# TRV_ANAREN_V0_2.net
KiCad netlist of a schematic drawn in EAGLE
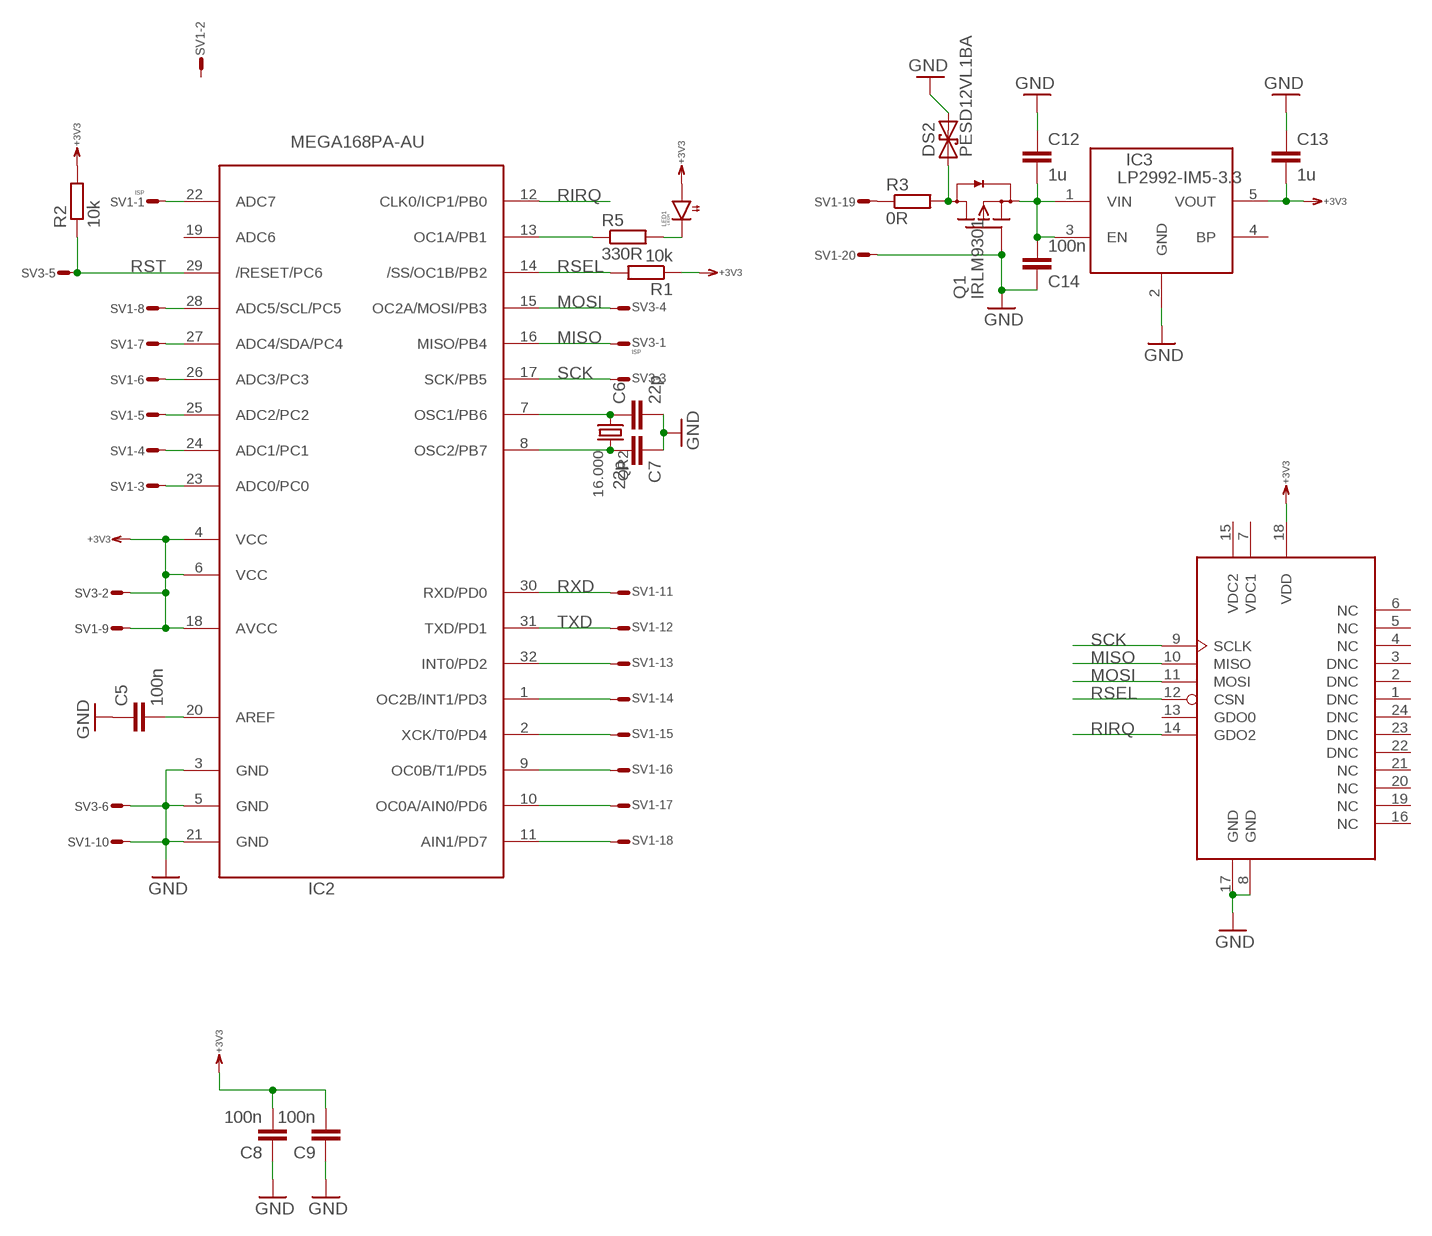
[diagram p0: schematic, sheet 1]

(export (version "E")
  (design (tool "Eeschema 10.0.6"))
  (components
    (comp (ref "C5")
      (value "100n")
      (footprint "eagle-import:0603")
      (libsource (lib "eagle-import") (part "C0603"))
    )
    (comp (ref "C6")
      (value "22p")
      (footprint "eagle-import:0603")
      (libsource (lib "eagle-import") (part "C0603"))
    )
    (comp (ref "C7")
      (value "22p")
      (footprint "eagle-import:0603")
      (libsource (lib "eagle-import") (part "C0603"))
    )
    (comp (ref "C8")
      (value "100n")
      (footprint "eagle-import:0603")
      (libsource (lib "eagle-import") (part "C0603"))
    )
    (comp (ref "C9")
      (value "100n")
      (footprint "eagle-import:0603")
      (libsource (lib "eagle-import") (part "C0603"))
    )
    (comp (ref "C12")
      (value "1u")
      (footprint "eagle-import:0603")
      (libsource (lib "eagle-import") (part "C0603"))
    )
    (comp (ref "C13")
      (value "1u")
      (footprint "eagle-import:0603")
      (libsource (lib "eagle-import") (part "C0603"))
    )
    (comp (ref "C14")
      (value "100n")
      (footprint "eagle-import:0603")
      (libsource (lib "eagle-import") (part "C0603"))
    )
    (comp (ref "DS2")
      (value "PESD12VL1BA")
      (footprint "eagle-import:SOD323")
      (libsource (lib "eagle-import") (part "TVS-U323"))
    )
    (comp (ref "IC2")
      (value "MEGA168PA-AU")
      (footprint "eagle-import:TQFP32-08")
      (libsource (lib "eagle-import") (part "MEGA168PA"))
    )
    (comp (ref "IC3")
      (value "LP2992-IM5-3.3")
      (footprint "eagle-import:SOT23-5")
      (libsource (lib "eagle-import") (part "LDO"))
    )
    (comp (ref "LED1")
      (value "LEDR")
      (footprint "eagle-import:0603")
      (libsource (lib "eagle-import") (part "LED0603"))
    )
    (comp (ref "Q1")
      (value "IRLM9301")
      (footprint "eagle-import:SOT23")
      (libsource (lib "eagle-import") (part "FET-PDSOT23"))
    )
    (comp (ref "QR2")
      (value "16.000")
      (footprint "eagle-import:HC49U-V")
      (libsource (lib "eagle-import") (part "Q49UV"))
    )
    (comp (ref "R1")
      (value "10k")
      (footprint "eagle-import:0603")
      (libsource (lib "eagle-import") (part "R0603"))
    )
    (comp (ref "R2")
      (value "10k")
      (footprint "eagle-import:0603")
      (libsource (lib "eagle-import") (part "R0603"))
    )
    (comp (ref "R3")
      (value "0R")
      (footprint "eagle-import:0603")
      (libsource (lib "eagle-import") (part "R0603"))
    )
    (comp (ref "R5")
      (value "330R")
      (footprint "eagle-import:0603")
      (libsource (lib "eagle-import") (part "R0603"))
    )
    (comp (ref "RF1")
      (value "ANAREN")
      (footprint "eagle-import:ANAREN")
      (libsource (lib "eagle-import") (part "ANAREN"))
    )
    (comp (ref "SV1")
      (value "ISP")
      (footprint "eagle-import:ML20")
      (libsource (lib "eagle-import") (part "ML20?E"))
    )
    (comp (ref "SV3")
      (value "ISP")
      (footprint "eagle-import:ML6")
      (libsource (lib "eagle-import") (part "ML6E"))
    )
  )
  (nets
    (net (code "1") (name "+3V3") (class "Default")
      (node (ref "C13") (pin "2") (pinfunction "2_2") (pintype "passive"))
      (node (ref "C8") (pin "2") (pinfunction "2_2") (pintype "passive"))
      (node (ref "C9") (pin "2") (pinfunction "2_2") (pintype "passive"))
      (node (ref "IC2") (pin "18") (pinfunction "AVCC_18") (pintype "bidirectional"))
      (node (ref "IC2") (pin "4") (pinfunction "VCC_4") (pintype "bidirectional"))
      (node (ref "IC2") (pin "6") (pinfunction "VCC_6") (pintype "bidirectional"))
      (node (ref "IC3") (pin "5") (pinfunction "VOUT_5") (pintype "bidirectional"))
      (node (ref "LED1") (pin "1") (pinfunction "A_1") (pintype "bidirectional"))
      (node (ref "R1") (pin "1") (pinfunction "1_1") (pintype "passive"))
      (node (ref "R2") (pin "2") (pinfunction "2_2") (pintype "passive"))
      (node (ref "RF1") (pin "18") (pinfunction "VDD_18") (pintype "bidirectional"))
      (node (ref "SV1") (pin "9") (pinfunction "S_9") (pintype "passive"))
      (node (ref "SV3") (pin "2") (pinfunction "S_2") (pintype "passive"))
    )
    (net (code "2") (name "/MISO") (class "Default")
      (node (ref "IC2") (pin "16") (pinfunction "MISO/PB4_16") (pintype "bidirectional"))
      (node (ref "RF1") (pin "10") (pinfunction "MISO_10") (pintype "output"))
      (node (ref "SV3") (pin "1") (pinfunction "S_1") (pintype "passive"))
    )
    (net (code "3") (name "/MOSI") (class "Default")
      (node (ref "IC2") (pin "15") (pinfunction "OC2A/MOSI/PB3_15") (pintype "bidirectional"))
      (node (ref "RF1") (pin "11") (pinfunction "MOSI_11") (pintype "input"))
      (node (ref "SV3") (pin "4") (pinfunction "S_4") (pintype "passive"))
    )
    (net (code "4") (name "/RIRQ") (class "Default")
      (node (ref "IC2") (pin "12") (pinfunction "CLK0/ICP1/PB0_12") (pintype "bidirectional"))
      (node (ref "RF1") (pin "14") (pinfunction "GDO2_14") (pintype "bidirectional"))
    )
    (net (code "5") (name "/RSEL") (class "Default")
      (node (ref "IC2") (pin "14") (pinfunction "/SS/OC1B/PB2_14") (pintype "bidirectional"))
      (node (ref "R1") (pin "2") (pinfunction "2_2") (pintype "passive"))
      (node (ref "RF1") (pin "12") (pinfunction "CSN_12") (pintype "input"))
    )
    (net (code "6") (name "/RST") (class "Default")
      (node (ref "IC2") (pin "29") (pinfunction "/RESET/PC6_29") (pintype "bidirectional"))
      (node (ref "R2") (pin "1") (pinfunction "1_1") (pintype "passive"))
      (node (ref "SV3") (pin "5") (pinfunction "S_5") (pintype "passive"))
    )
    (net (code "7") (name "/RXD") (class "Default")
      (node (ref "IC2") (pin "30") (pinfunction "RXD/PD0_30") (pintype "bidirectional"))
      (node (ref "SV1") (pin "11") (pinfunction "S_11") (pintype "passive"))
    )
    (net (code "8") (name "/SCK") (class "Default")
      (node (ref "IC2") (pin "17") (pinfunction "SCK/PB5_17") (pintype "bidirectional"))
      (node (ref "RF1") (pin "9") (pinfunction "SCLK_9") (pintype "input"))
      (node (ref "SV3") (pin "3") (pinfunction "S_3") (pintype "passive"))
    )
    (net (code "9") (name "/TXD") (class "Default")
      (node (ref "IC2") (pin "31") (pinfunction "TXD/PD1_31") (pintype "bidirectional"))
      (node (ref "SV1") (pin "12") (pinfunction "S_12") (pintype "passive"))
    )
    (net (code "10") (name "GND") (class "Default")
      (node (ref "C12") (pin "1") (pinfunction "1_1") (pintype "passive"))
      (node (ref "C13") (pin "1") (pinfunction "1_1") (pintype "passive"))
      (node (ref "C14") (pin "1") (pinfunction "1_1") (pintype "passive"))
      (node (ref "C5") (pin "1") (pinfunction "1_1") (pintype "passive"))
      (node (ref "C6") (pin "2") (pinfunction "2_2") (pintype "passive"))
      (node (ref "C7") (pin "1") (pinfunction "1_1") (pintype "passive"))
      (node (ref "C8") (pin "1") (pinfunction "1_1") (pintype "passive"))
      (node (ref "C9") (pin "1") (pinfunction "1_1") (pintype "passive"))
      (node (ref "DS2") (pin "C") (pinfunction "2_C") (pintype "passive"))
      (node (ref "IC2") (pin "21") (pinfunction "GND_21") (pintype "bidirectional"))
      (node (ref "IC2") (pin "3") (pinfunction "GND_3") (pintype "bidirectional"))
      (node (ref "IC2") (pin "5") (pinfunction "GND_5") (pintype "bidirectional"))
      (node (ref "IC3") (pin "2") (pinfunction "GND_2") (pintype "bidirectional"))
      (node (ref "Q1") (pin "1") (pinfunction "G_1") (pintype "passive"))
      (node (ref "RF1") (pin "17") (pinfunction "GND_17") (pintype "bidirectional"))
      (node (ref "RF1") (pin "8") (pinfunction "GND_8") (pintype "bidirectional"))
      (node (ref "SV1") (pin "10") (pinfunction "S_10") (pintype "passive"))
      (node (ref "SV1") (pin "20") (pinfunction "S_20") (pintype "passive"))
      (node (ref "SV3") (pin "6") (pinfunction "S_6") (pintype "passive"))
    )
    (net (code "11") (name "Net-(DS2-1)") (class "Default")
      (node (ref "DS2") (pin "A") (pinfunction "1_A") (pintype "passive"))
      (node (ref "Q1") (pin "3") (pinfunction "D_3") (pintype "passive"))
      (node (ref "R3") (pin "2") (pinfunction "2_2") (pintype "passive"))
    )
    (net (code "12") (name "Net-(IC2-ADC0{slash}PC0)") (class "Default")
      (node (ref "IC2") (pin "23") (pinfunction "ADC0/PC0_23") (pintype "bidirectional"))
      (node (ref "SV1") (pin "3") (pinfunction "S_3") (pintype "passive"))
    )
    (net (code "13") (name "Net-(IC2-ADC1{slash}PC1)") (class "Default")
      (node (ref "IC2") (pin "24") (pinfunction "ADC1/PC1_24") (pintype "bidirectional"))
      (node (ref "SV1") (pin "4") (pinfunction "S_4") (pintype "passive"))
    )
    (net (code "14") (name "Net-(IC2-ADC2{slash}PC2)") (class "Default")
      (node (ref "IC2") (pin "25") (pinfunction "ADC2/PC2_25") (pintype "bidirectional"))
      (node (ref "SV1") (pin "5") (pinfunction "S_5") (pintype "passive"))
    )
    (net (code "15") (name "Net-(IC2-ADC3{slash}PC3)") (class "Default")
      (node (ref "IC2") (pin "26") (pinfunction "ADC3/PC3_26") (pintype "bidirectional"))
      (node (ref "SV1") (pin "6") (pinfunction "S_6") (pintype "passive"))
    )
    (net (code "16") (name "Net-(IC2-ADC4{slash}SDA{slash}PC4)") (class "Default")
      (node (ref "IC2") (pin "27") (pinfunction "ADC4/SDA/PC4_27") (pintype "bidirectional"))
      (node (ref "SV1") (pin "7") (pinfunction "S_7") (pintype "passive"))
    )
    (net (code "17") (name "Net-(IC2-ADC5{slash}SCL{slash}PC5)") (class "Default")
      (node (ref "IC2") (pin "28") (pinfunction "ADC5/SCL/PC5_28") (pintype "bidirectional"))
      (node (ref "SV1") (pin "8") (pinfunction "S_8") (pintype "passive"))
    )
    (net (code "18") (name "Net-(IC2-ADC7)") (class "Default")
      (node (ref "IC2") (pin "22") (pinfunction "ADC7_22") (pintype "bidirectional"))
      (node (ref "SV1") (pin "1") (pinfunction "S_1") (pintype "passive"))
    )
    (net (code "19") (name "Net-(IC2-AIN1{slash}PD7)") (class "Default")
      (node (ref "IC2") (pin "11") (pinfunction "AIN1/PD7_11") (pintype "bidirectional"))
      (node (ref "SV1") (pin "18") (pinfunction "S_18") (pintype "passive"))
    )
    (net (code "20") (name "Net-(IC2-AREF)") (class "Default")
      (node (ref "C5") (pin "2") (pinfunction "2_2") (pintype "passive"))
      (node (ref "IC2") (pin "20") (pinfunction "AREF_20") (pintype "bidirectional"))
    )
    (net (code "21") (name "Net-(IC2-INT0{slash}PD2)") (class "Default")
      (node (ref "IC2") (pin "32") (pinfunction "INT0/PD2_32") (pintype "bidirectional"))
      (node (ref "SV1") (pin "13") (pinfunction "S_13") (pintype "passive"))
    )
    (net (code "22") (name "Net-(IC2-OC0A{slash}AIN0{slash}PD6)") (class "Default")
      (node (ref "IC2") (pin "10") (pinfunction "OC0A/AIN0/PD6_10") (pintype "bidirectional"))
      (node (ref "SV1") (pin "17") (pinfunction "S_17") (pintype "passive"))
    )
    (net (code "23") (name "Net-(IC2-OC0B{slash}T1{slash}PD5)") (class "Default")
      (node (ref "IC2") (pin "9") (pinfunction "OC0B/T1/PD5_9") (pintype "bidirectional"))
      (node (ref "SV1") (pin "16") (pinfunction "S_16") (pintype "passive"))
    )
    (net (code "24") (name "Net-(IC2-OC1A{slash}PB1)") (class "Default")
      (node (ref "IC2") (pin "13") (pinfunction "OC1A/PB1_13") (pintype "bidirectional"))
      (node (ref "R5") (pin "1") (pinfunction "1_1") (pintype "passive"))
    )
    (net (code "25") (name "Net-(IC2-OC2B{slash}INT1{slash}PD3)") (class "Default")
      (node (ref "IC2") (pin "1") (pinfunction "OC2B/INT1/PD3_1") (pintype "bidirectional"))
      (node (ref "SV1") (pin "14") (pinfunction "S_14") (pintype "passive"))
    )
    (net (code "26") (name "Net-(IC2-OSC1{slash}PB6)") (class "Default")
      (node (ref "C6") (pin "1") (pinfunction "1_1") (pintype "passive"))
      (node (ref "IC2") (pin "7") (pinfunction "OSC1/PB6_7") (pintype "bidirectional"))
      (node (ref "QR2") (pin "1") (pinfunction "1_1") (pintype "passive"))
    )
    (net (code "27") (name "Net-(IC2-OSC2{slash}PB7)") (class "Default")
      (node (ref "C7") (pin "2") (pinfunction "2_2") (pintype "passive"))
      (node (ref "IC2") (pin "8") (pinfunction "OSC2/PB7_8") (pintype "bidirectional"))
      (node (ref "QR2") (pin "2") (pinfunction "2_2") (pintype "passive"))
    )
    (net (code "28") (name "Net-(IC2-XCK{slash}T0{slash}PD4)") (class "Default")
      (node (ref "IC2") (pin "2") (pinfunction "XCK/T0/PD4_2") (pintype "bidirectional"))
      (node (ref "SV1") (pin "15") (pinfunction "S_15") (pintype "passive"))
    )
    (net (code "29") (name "Net-(IC3-EN)") (class "Default")
      (node (ref "C12") (pin "2") (pinfunction "2_2") (pintype "passive"))
      (node (ref "C14") (pin "2") (pinfunction "2_2") (pintype "passive"))
      (node (ref "IC3") (pin "1") (pinfunction "VIN_1") (pintype "bidirectional"))
      (node (ref "IC3") (pin "3") (pinfunction "EN_3") (pintype "bidirectional"))
      (node (ref "Q1") (pin "2") (pinfunction "S_2") (pintype "passive"))
    )
    (net (code "30") (name "Net-(LED1-C)") (class "Default")
      (node (ref "LED1") (pin "2") (pinfunction "C_2") (pintype "bidirectional"))
      (node (ref "R5") (pin "2") (pinfunction "2_2") (pintype "passive"))
    )
    (net (code "31") (name "Net-(SV1K-S)") (class "Default")
      (node (ref "R3") (pin "1") (pinfunction "1_1") (pintype "passive"))
      (node (ref "SV1") (pin "19") (pinfunction "S_19") (pintype "passive"))
    )
    (net (code "32") (name "unconnected-(IC2-ADC6-Pad19)") (class "Default")
      (node (ref "IC2") (pin "19") (pinfunction "ADC6_19") (pintype "bidirectional"))
    )
    (net (code "33") (name "unconnected-(IC3-BP-Pad4)") (class "Default")
      (node (ref "IC3") (pin "4") (pinfunction "BP_4") (pintype "bidirectional"))
    )
    (net (code "34") (name "unconnected-(RF1-DNC-Pad1)") (class "Default")
      (node (ref "RF1") (pin "1") (pinfunction "DNC_1") (pintype "bidirectional"))
    )
    (net (code "35") (name "unconnected-(RF1-DNC-Pad2)") (class "Default")
      (node (ref "RF1") (pin "2") (pinfunction "DNC_2") (pintype "bidirectional"))
    )
    (net (code "36") (name "unconnected-(RF1-DNC-Pad3)") (class "Default")
      (node (ref "RF1") (pin "3") (pinfunction "DNC_3") (pintype "bidirectional"))
    )
    (net (code "37") (name "unconnected-(RF1-DNC-Pad22)") (class "Default")
      (node (ref "RF1") (pin "22") (pinfunction "DNC_22") (pintype "bidirectional"))
    )
    (net (code "38") (name "unconnected-(RF1-DNC-Pad23)") (class "Default")
      (node (ref "RF1") (pin "23") (pinfunction "DNC_23") (pintype "bidirectional"))
    )
    (net (code "39") (name "unconnected-(RF1-DNC-Pad24)") (class "Default")
      (node (ref "RF1") (pin "24") (pinfunction "DNC_24") (pintype "bidirectional"))
    )
    (net (code "40") (name "unconnected-(RF1-GDO0-Pad13)") (class "Default")
      (node (ref "RF1") (pin "13") (pinfunction "GDO0_13") (pintype "bidirectional"))
    )
    (net (code "41") (name "unconnected-(RF1-NC-Pad4)") (class "Default")
      (node (ref "RF1") (pin "4") (pinfunction "NC_4") (pintype "bidirectional"))
    )
    (net (code "42") (name "unconnected-(RF1-NC-Pad5)") (class "Default")
      (node (ref "RF1") (pin "5") (pinfunction "NC_5") (pintype "bidirectional"))
    )
    (net (code "43") (name "unconnected-(RF1-NC-Pad6)") (class "Default")
      (node (ref "RF1") (pin "6") (pinfunction "NC_6") (pintype "bidirectional"))
    )
    (net (code "44") (name "unconnected-(RF1-NC-Pad16)") (class "Default")
      (node (ref "RF1") (pin "16") (pinfunction "NC_16") (pintype "bidirectional"))
    )
    (net (code "45") (name "unconnected-(RF1-NC-Pad19)") (class "Default")
      (node (ref "RF1") (pin "19") (pinfunction "NC_19") (pintype "bidirectional"))
    )
    (net (code "46") (name "unconnected-(RF1-NC-Pad20)") (class "Default")
      (node (ref "RF1") (pin "20") (pinfunction "NC_20") (pintype "bidirectional"))
    )
    (net (code "47") (name "unconnected-(RF1-NC-Pad21)") (class "Default")
      (node (ref "RF1") (pin "21") (pinfunction "NC_21") (pintype "bidirectional"))
    )
    (net (code "48") (name "unconnected-(RF1-VDC1-Pad7)") (class "Default")
      (node (ref "RF1") (pin "7") (pinfunction "VDC1_7") (pintype "bidirectional"))
    )
    (net (code "49") (name "unconnected-(RF1-VDC2-Pad15)") (class "Default")
      (node (ref "RF1") (pin "15") (pinfunction "VDC2_15") (pintype "bidirectional"))
    )
    (net (code "50") (name "unconnected-(SV1L-S-Pad2)") (class "Default")
      (node (ref "SV1") (pin "2") (pinfunction "S_2") (pintype "passive"))
    )
  )
)
